# POWER.net
KiCad netlist of a schematic drawn in Altium Designer
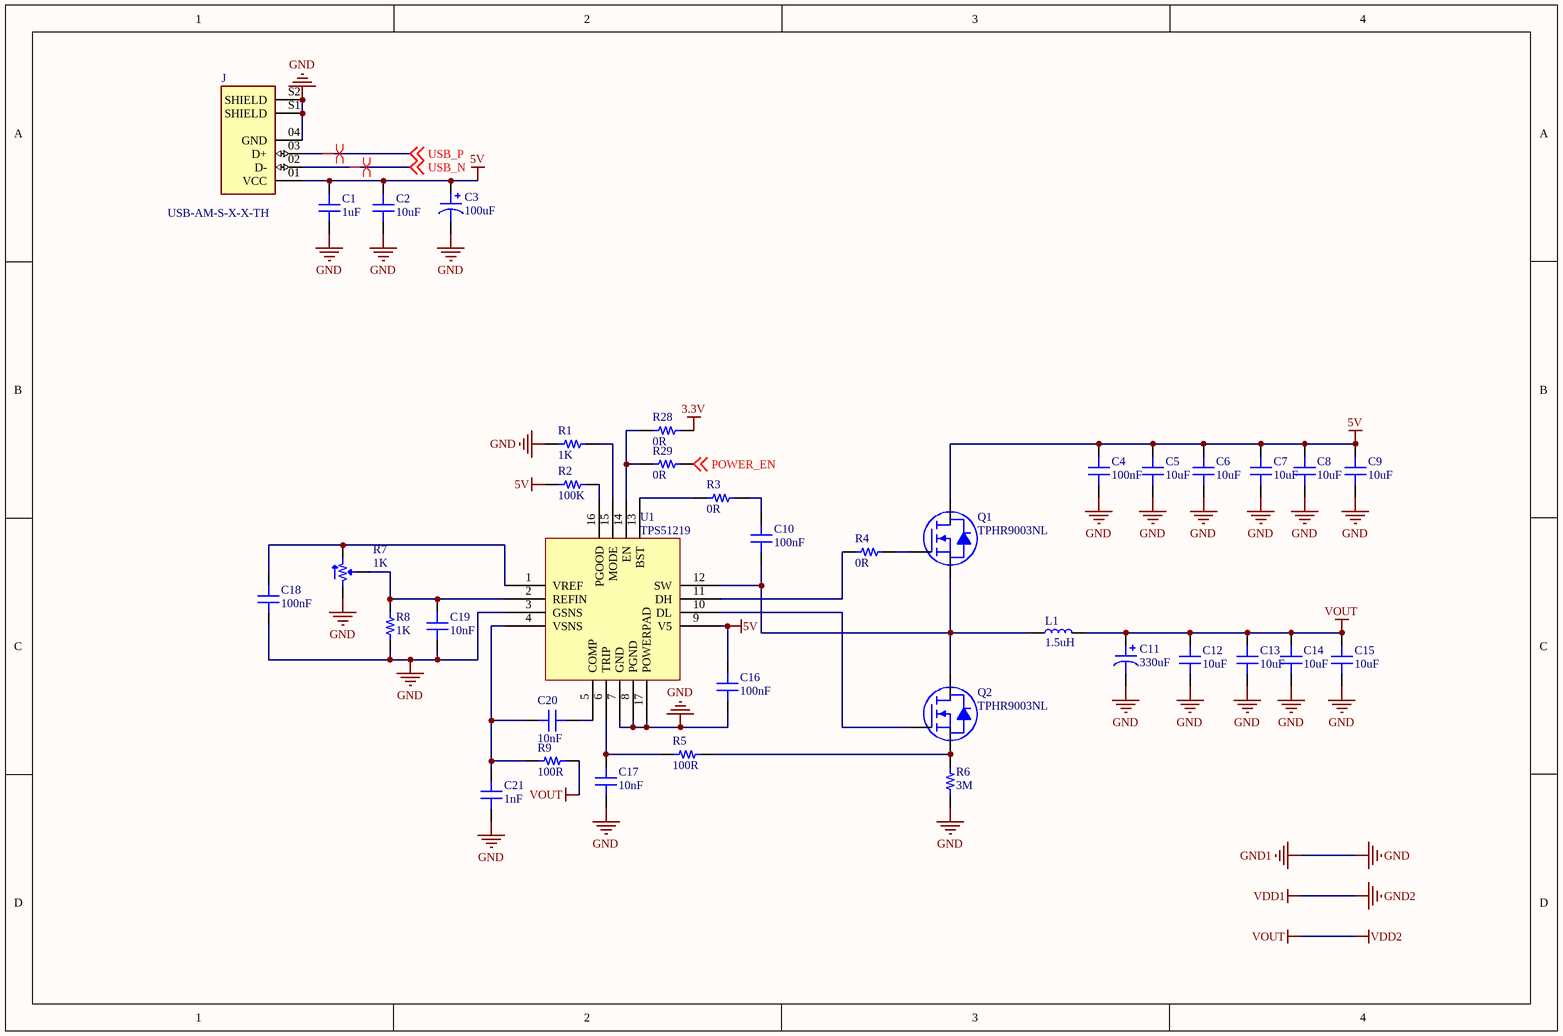
[diagram p0: POWER.SchDoc]

(export (version "E")
  (design (tool "Eeschema 10.0.6"))
  (components
    (comp (ref "C1") (value "1uF") (footprint "CAP_SMD_1206") (libsource (lib "USB_MINER") (part "CAP")))
    (comp (ref "C2") (value "10uF") (footprint "CAP_SMD_1206") (libsource (lib "USB_MINER") (part "CAP")))
    (comp (ref "C3")
      (value "100uF")
      (footprint "CAP-TAN-CASE-B")
      (libsource (lib "USB_MINER") (part "POLARIZED CAP"))
    )
    (comp (ref "C4") (value "100nF") (footprint "CAP-SMD-0603") (libsource (lib "USB_MINER") (part "CAP")))
    (comp (ref "C5") (value "10uF") (footprint "CAP-SMD-0603") (libsource (lib "USB_MINER") (part "CAP")))
    (comp (ref "C6") (value "10uF") (footprint "CAP-SMD-0603") (libsource (lib "USB_MINER") (part "CAP")))
    (comp (ref "C7") (value "10uF") (footprint "CAP-SMD-0603") (libsource (lib "USB_MINER") (part "CAP")))
    (comp (ref "C8") (value "10uF") (footprint "CAP-SMD-0603") (libsource (lib "USB_MINER") (part "CAP")))
    (comp (ref "C9") (value "10uF") (footprint "CAP-SMD-0603") (libsource (lib "USB_MINER") (part "CAP")))
    (comp (ref "C10") (value "100nF") (footprint "CAP-SMD-0603") (libsource (lib "USB_MINER") (part "CAP")))
    (comp (ref "C11")
      (value "330uF")
      (footprint "CAP-TAN-CASE-E")
      (libsource (lib "USB_MINER") (part "POLARIZED CAP"))
    )
    (comp (ref "C12") (value "10uF") (footprint "CAP-SMD-0603") (libsource (lib "USB_MINER") (part "CAP")))
    (comp (ref "C13") (value "10uF") (footprint "CAP-SMD-0603") (libsource (lib "USB_MINER") (part "CAP")))
    (comp (ref "C14") (value "10uF") (footprint "CAP-SMD-0603") (libsource (lib "USB_MINER") (part "CAP")))
    (comp (ref "C15") (value "10uF") (footprint "CAP-SMD-0603") (libsource (lib "USB_MINER") (part "CAP")))
    (comp (ref "C16") (value "100nF") (footprint "CAP-SMD-0603") (libsource (lib "USB_MINER") (part "CAP")))
    (comp (ref "C17") (value "10nF") (footprint "CAP-SMD-0603") (libsource (lib "USB_MINER") (part "CAP")))
    (comp (ref "C18") (value "100nF") (footprint "CAP-SMD-0603") (libsource (lib "USB_MINER") (part "CAP")))
    (comp (ref "C19") (value "10nF") (footprint "CAP-SMD-0603") (libsource (lib "USB_MINER") (part "CAP")))
    (comp (ref "C20") (value "10nF") (footprint "CAP-SMD-0603") (libsource (lib "USB_MINER") (part "CAP")))
    (comp (ref "C21") (value "1nF") (footprint "CAP-SMD-0603") (libsource (lib "USB_MINER") (part "CAP")))
    (comp (ref "J")
      (value "USB-AM-S-X-X-TH")
      (footprint "SAMTEC_USB-AM-S-X-X-TH")
      (description "USB-A (USB TYPE-A) USB 2.0 Plug Connector 4 Position Through Hole, Right Angle")
      (fields (field (name "MF") "Samtec") (field (name "MP") "USB-AM-S-F-B-TH"))
      (libsource (lib "USB_MINER") (part "USB-AM-S-X-X-TH"))
    )
    (comp (ref "L1") (value "1.5uH") (footprint "IND") (libsource (lib "USB_MINER") (part "INDUCTOR")))
    (comp (ref "Q1")
      (value "TPHR9003NL")
      (footprint "ADVANCE SOP")
      (libsource (lib "USB_MINER") (part "MOSFET-N"))
    )
    (comp (ref "Q2")
      (value "TPHR9003NL")
      (footprint "ADVANCE SOP")
      (libsource (lib "USB_MINER") (part "MOSFET-N"))
    )
    (comp (ref "R1") (value "1K") (footprint "RES-SMD-0402") (libsource (lib "USB_MINER") (part "RES")))
    (comp (ref "R2") (value "100K") (footprint "RES-SMD-0402") (libsource (lib "USB_MINER") (part "RES")))
    (comp (ref "R3") (value "0R") (footprint "RES-SMD-0402") (libsource (lib "USB_MINER") (part "RES")))
    (comp (ref "R4") (value "0R") (footprint "RES-SMD-0402") (libsource (lib "USB_MINER") (part "RES")))
    (comp (ref "R5") (value "100R") (footprint "RES-SMD-0402") (libsource (lib "USB_MINER") (part "RES")))
    (comp (ref "R6") (value "3M") (footprint "RES-SMD-0402") (libsource (lib "USB_MINER") (part "RES")))
    (comp (ref "R7")
      (value "1K")
      (footprint "POT")
      (description "Potentiometer")
      (libsource (lib "USB_MINER") (part "Potentiometer"))
    )
    (comp (ref "R8") (value "1K") (footprint "RES-SMD-0402") (libsource (lib "USB_MINER") (part "RES")))
    (comp (ref "R9") (value "100R") (footprint "RES-SMD-0402") (libsource (lib "USB_MINER") (part "RES")))
    (comp (ref "R28") (value "0R") (footprint "RES-SMD-0402") (libsource (lib "USB_MINER") (part "RES")))
    (comp (ref "R29") (value "0R") (footprint "RES-SMD-0402") (libsource (lib "USB_MINER") (part "RES")))
    (comp (ref "U1")
      (value "TPS51219")
      (footprint "QFN50P300X300X80-17N")
      (libsource (lib "USB_MINER") (part "TPS51219"))
    )
  )
  (nets
    (net (code "1") (name "3.3V") (class "Default")
      (node (ref "R28") (pin "2") (pinfunction "2_2") (pintype "passive"))
    )
    (net (code "2") (name "5V") (class "Default")
      (node (ref "C1") (pin "1") (pinfunction "1_1") (pintype "passive"))
      (node (ref "C16") (pin "1") (pinfunction "1_1") (pintype "passive"))
      (node (ref "C2") (pin "1") (pinfunction "1_1") (pintype "passive"))
      (node (ref "C3") (pin "1") (pinfunction "1_1") (pintype "passive"))
      (node (ref "C4") (pin "1") (pinfunction "1_1") (pintype "passive"))
      (node (ref "C5") (pin "1") (pinfunction "1_1") (pintype "passive"))
      (node (ref "C6") (pin "1") (pinfunction "1_1") (pintype "passive"))
      (node (ref "C7") (pin "1") (pinfunction "1_1") (pintype "passive"))
      (node (ref "C8") (pin "1") (pinfunction "1_1") (pintype "passive"))
      (node (ref "C9") (pin "1") (pinfunction "1_1") (pintype "passive"))
      (node (ref "J") (pin "01") (pinfunction "VCC_01") (pintype "power_in"))
      (node (ref "Q1") (pin "D") (pinfunction "D_D") (pintype "passive"))
      (node (ref "R2") (pin "2") (pinfunction "2_2") (pintype "passive"))
      (node (ref "U1") (pin "9") (pinfunction "V5_9") (pintype "passive"))
    )
    (net (code "3") (name "GND") (class "Default")
      (node (ref "C1") (pin "2") (pinfunction "2_2") (pintype "passive"))
      (node (ref "C11") (pin "2") (pinfunction "2_2") (pintype "passive"))
      (node (ref "C12") (pin "2") (pinfunction "2_2") (pintype "passive"))
      (node (ref "C13") (pin "2") (pinfunction "2_2") (pintype "passive"))
      (node (ref "C14") (pin "2") (pinfunction "2_2") (pintype "passive"))
      (node (ref "C15") (pin "2") (pinfunction "2_2") (pintype "passive"))
      (node (ref "C16") (pin "2") (pinfunction "2_2") (pintype "passive"))
      (node (ref "C17") (pin "2") (pinfunction "2_2") (pintype "passive"))
      (node (ref "C18") (pin "1") (pinfunction "1_1") (pintype "passive"))
      (node (ref "C19") (pin "1") (pinfunction "1_1") (pintype "passive"))
      (node (ref "C2") (pin "2") (pinfunction "2_2") (pintype "passive"))
      (node (ref "C21") (pin "1") (pinfunction "1_1") (pintype "passive"))
      (node (ref "C3") (pin "2") (pinfunction "2_2") (pintype "passive"))
      (node (ref "C4") (pin "2") (pinfunction "2_2") (pintype "passive"))
      (node (ref "C5") (pin "2") (pinfunction "2_2") (pintype "passive"))
      (node (ref "C6") (pin "2") (pinfunction "2_2") (pintype "passive"))
      (node (ref "C7") (pin "2") (pinfunction "2_2") (pintype "passive"))
      (node (ref "C8") (pin "2") (pinfunction "2_2") (pintype "passive"))
      (node (ref "C9") (pin "2") (pinfunction "2_2") (pintype "passive"))
      (node (ref "J") (pin "04") (pinfunction "GND_04") (pintype "power_in"))
      (node (ref "J") (pin "S1") (pinfunction "SHIELD_S1") (pintype "passive"))
      (node (ref "J") (pin "S2") (pinfunction "SHIELD_S2") (pintype "passive"))
      (node (ref "R1") (pin "2") (pinfunction "2_2") (pintype "passive"))
      (node (ref "R6") (pin "2") (pinfunction "2_2") (pintype "passive"))
      (node (ref "R7") (pin "1") (pinfunction "1_1") (pintype "passive"))
      (node (ref "R8") (pin "2") (pinfunction "2_2") (pintype "passive"))
      (node (ref "U1") (pin "17") (pinfunction "POWERPAD_17") (pintype "passive"))
      (node (ref "U1") (pin "3") (pinfunction "GSNS_3") (pintype "passive"))
      (node (ref "U1") (pin "7") (pinfunction "GND_7") (pintype "passive"))
      (node (ref "U1") (pin "8") (pinfunction "PGND_8") (pintype "passive"))
    )
    (net (code "5") (name "Net-(C10-Pad1)") (class "Default")
      (node (ref "C10") (pin "1") (pinfunction "1_1") (pintype "passive"))
      (node (ref "R3") (pin "1") (pinfunction "1_1") (pintype "passive"))
    )
    (net (code "6") (name "Net-(Q1-PadG)") (class "Default")
      (node (ref "Q1") (pin "G") (pinfunction "G_G") (pintype "passive"))
      (node (ref "R4") (pin "1") (pinfunction "1_1") (pintype "passive"))
    )
    (net (code "7") (name "Net-(Q2-PadS)") (class "Default")
      (node (ref "Q2") (pin "S") (pinfunction "S_S") (pintype "passive"))
      (node (ref "R5") (pin "1") (pinfunction "1_1") (pintype "passive"))
      (node (ref "R6") (pin "1") (pinfunction "1_1") (pintype "passive"))
    )
    (net (code "8") (name "Net-(U1-BST)") (class "Default")
      (node (ref "R3") (pin "2") (pinfunction "2_2") (pintype "passive"))
      (node (ref "U1") (pin "13") (pinfunction "BST_13") (pintype "passive"))
    )
    (net (code "9") (name "Net-(U1-COMP)") (class "Default")
      (node (ref "C20") (pin "2") (pinfunction "2_2") (pintype "passive"))
      (node (ref "U1") (pin "5") (pinfunction "COMP_5") (pintype "passive"))
    )
    (net (code "10") (name "Net-(U1-DH)") (class "Default")
      (node (ref "R4") (pin "2") (pinfunction "2_2") (pintype "passive"))
      (node (ref "U1") (pin "11") (pinfunction "DH_11") (pintype "passive"))
    )
    (net (code "11") (name "Net-(U1-DL)") (class "Default")
      (node (ref "Q2") (pin "G") (pinfunction "G_G") (pintype "passive"))
      (node (ref "U1") (pin "10") (pinfunction "DL_10") (pintype "passive"))
    )
    (net (code "12") (name "Net-(U1-EN)") (class "Default")
      (node (ref "R28") (pin "1") (pinfunction "1_1") (pintype "passive"))
      (node (ref "R29") (pin "1") (pinfunction "1_1") (pintype "passive"))
      (node (ref "U1") (pin "14") (pinfunction "EN_14") (pintype "passive"))
    )
    (net (code "13") (name "Net-(U1-MODE)") (class "Default")
      (node (ref "R1") (pin "1") (pinfunction "1_1") (pintype "passive"))
      (node (ref "U1") (pin "15") (pinfunction "MODE_15") (pintype "passive"))
    )
    (net (code "14") (name "Net-(U1-PGOOD)") (class "Default")
      (node (ref "R2") (pin "1") (pinfunction "1_1") (pintype "passive"))
      (node (ref "U1") (pin "16") (pinfunction "PGOOD_16") (pintype "passive"))
    )
    (net (code "15") (name "Net-(U1-REFIN)") (class "Default")
      (node (ref "C19") (pin "2") (pinfunction "2_2") (pintype "passive"))
      (node (ref "R7") (pin "2") (pinfunction "2_2") (pintype "passive"))
      (node (ref "R8") (pin "1") (pinfunction "1_1") (pintype "passive"))
      (node (ref "U1") (pin "2") (pinfunction "REFIN_2") (pintype "passive"))
    )
    (net (code "16") (name "Net-(U1-SW)") (class "Default")
      (node (ref "C10") (pin "2") (pinfunction "2_2") (pintype "passive"))
      (node (ref "L1") (pin "1") (pinfunction "1_1") (pintype "passive"))
      (node (ref "Q1") (pin "S") (pinfunction "S_S") (pintype "passive"))
      (node (ref "Q2") (pin "D") (pinfunction "D_D") (pintype "passive"))
      (node (ref "U1") (pin "12") (pinfunction "SW_12") (pintype "passive"))
    )
    (net (code "17") (name "Net-(U1-TRIP)") (class "Default")
      (node (ref "C17") (pin "1") (pinfunction "1_1") (pintype "passive"))
      (node (ref "R5") (pin "2") (pinfunction "2_2") (pintype "passive"))
      (node (ref "U1") (pin "6") (pinfunction "TRIP_6") (pintype "passive"))
    )
    (net (code "18") (name "Net-(U1-VREF)") (class "Default")
      (node (ref "C18") (pin "2") (pinfunction "2_2") (pintype "passive"))
      (node (ref "R7") (pin "3") (pinfunction "3_3") (pintype "passive"))
      (node (ref "U1") (pin "1") (pinfunction "VREF_1") (pintype "passive"))
    )
    (net (code "19") (name "Net-(U1-VSNS)") (class "Default")
      (node (ref "C20") (pin "1") (pinfunction "1_1") (pintype "passive"))
      (node (ref "C21") (pin "2") (pinfunction "2_2") (pintype "passive"))
      (node (ref "R9") (pin "2") (pinfunction "2_2") (pintype "passive"))
      (node (ref "U1") (pin "4") (pinfunction "VSNS_4") (pintype "passive"))
    )
    (net (code "20") (name "POWER_EN") (class "Default")
      (node (ref "R29") (pin "2") (pinfunction "2_2") (pintype "passive"))
    )
    (net (code "21") (name "USB_N") (class "Default")
      (node (ref "J") (pin "02") (pinfunction "D-_02") (pintype "bidirectional"))
    )
    (net (code "22") (name "USB_P") (class "Default")
      (node (ref "J") (pin "03") (pinfunction "D+_03") (pintype "bidirectional"))
    )
    (net (code "23") (name "VDD2") (class "Default")
      (node (ref "C11") (pin "1") (pinfunction "1_1") (pintype "passive"))
      (node (ref "C12") (pin "1") (pinfunction "1_1") (pintype "passive"))
      (node (ref "C13") (pin "1") (pinfunction "1_1") (pintype "passive"))
      (node (ref "C14") (pin "1") (pinfunction "1_1") (pintype "passive"))
      (node (ref "C15") (pin "1") (pinfunction "1_1") (pintype "passive"))
      (node (ref "L1") (pin "2") (pinfunction "2_2") (pintype "passive"))
      (node (ref "R9") (pin "1") (pinfunction "1_1") (pintype "passive"))
    )
  )
)
